# SSB_Transceiver_IF_Amplifier.net
KiCad netlist of a schematic drawn in EAGLE
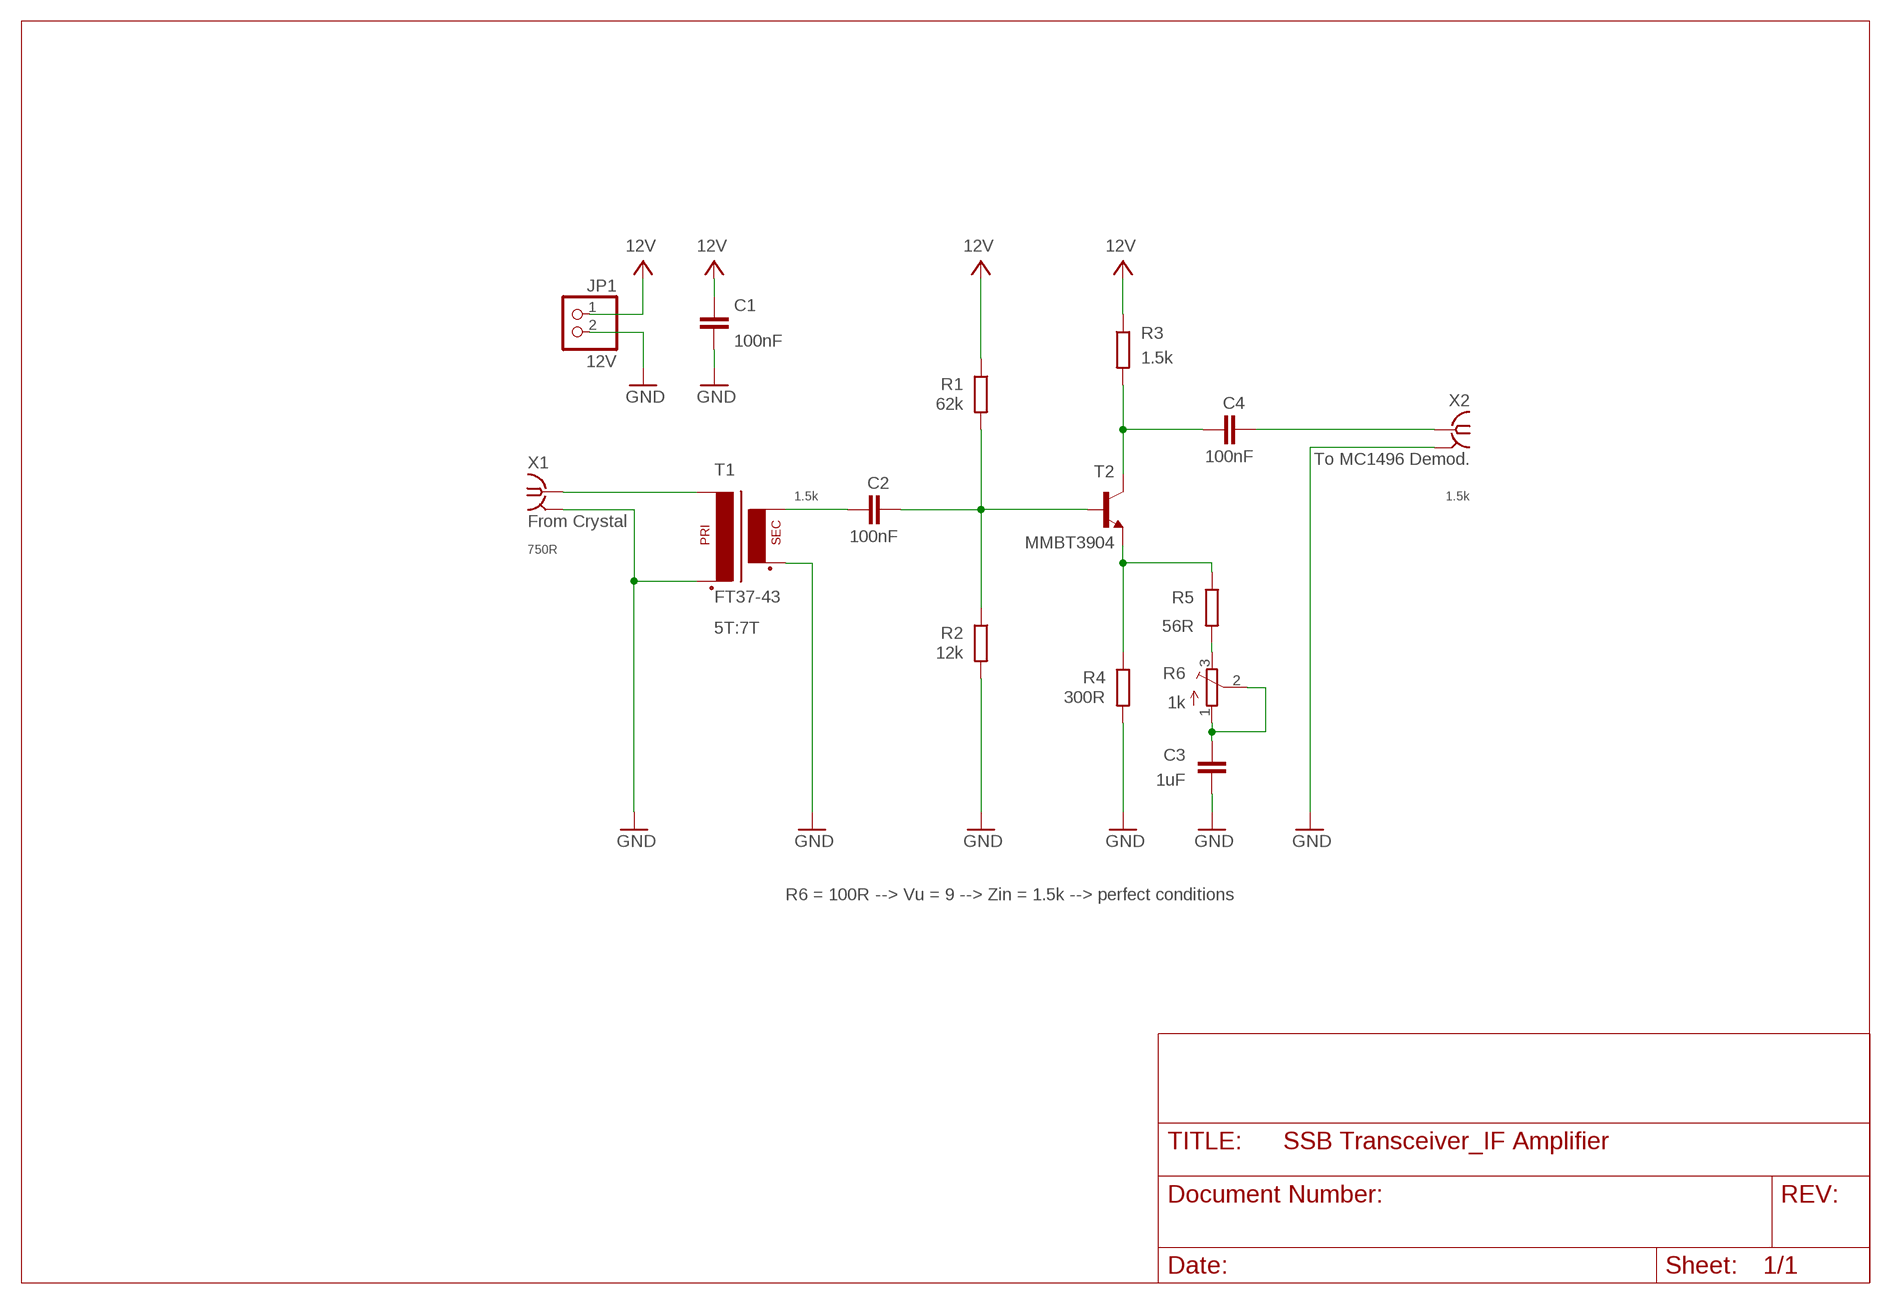
[diagram p0: schematic, sheet 1]

(export (version "E")
  (design (tool "Eeschema 10.0.6"))
  (components
    (comp (ref "C1")
      (value "100nF")
      (footprint "eagle-import:C0805")
      (libsource (lib "eagle-import") (part "C-EUC0805"))
    )
    (comp (ref "C2")
      (value "100nF")
      (footprint "eagle-import:C0805")
      (libsource (lib "eagle-import") (part "C-EUC0805"))
    )
    (comp (ref "C3")
      (value "1uF")
      (footprint "eagle-import:C0805")
      (libsource (lib "eagle-import") (part "C-EUC0805"))
    )
    (comp (ref "C4")
      (value "100nF")
      (footprint "eagle-import:C0805")
      (libsource (lib "eagle-import") (part "C-EUC0805"))
    )
    (comp (ref "JP1")
      (value "12V")
      (footprint "eagle-import:1X02")
      (libsource (lib "eagle-import") (part "PINHD-1X2"))
    )
    (comp (ref "R1")
      (value "62k")
      (footprint "eagle-import:R0805")
      (libsource (lib "eagle-import") (part "R-EU_R0805"))
    )
    (comp (ref "R2")
      (value "12k")
      (footprint "eagle-import:R0805")
      (libsource (lib "eagle-import") (part "R-EU_R0805"))
    )
    (comp (ref "R3")
      (value "1.5k")
      (footprint "eagle-import:R0805")
      (libsource (lib "eagle-import") (part "R-EU_R0805"))
    )
    (comp (ref "R4")
      (value "300R")
      (footprint "eagle-import:R0805")
      (libsource (lib "eagle-import") (part "R-EU_R0805"))
    )
    (comp (ref "R5")
      (value "56R")
      (footprint "eagle-import:R0805")
      (libsource (lib "eagle-import") (part "R-EU_R0805"))
    )
    (comp (ref "R6")
      (value "1k")
      (footprint "eagle-import:3223G")
      (libsource (lib "eagle-import") (part "TRIM_EU-3223G"))
    )
    (comp (ref "T1")
      (value "FT37-43")
      (footprint "eagle-import:FT37-43SMD")
      (libsource (lib "eagle-import") (part "FT37-43"))
    )
    (comp (ref "T2")
      (value "MMBT3904")
      (footprint "eagle-import:SOT23-BEC")
      (libsource (lib "eagle-import") (part "-NPN-SOT23-BECMMBT3904LT1"))
    )
    (comp (ref "X1")
      (value "From Crystal")
      (footprint "eagle-import:J502-ND-142-0711-821_826")
      (fields (field (name "MF") "JOHNSON COMPONENTS") (field (name "MPN") "142-0711-821"))
      (libsource (lib "eagle-import") (part "SMA-PCB-CON142-0711-821/826"))
    )
    (comp (ref "X2")
      (value "To MC1496 Demod.")
      (footprint "eagle-import:J502-ND-142-0711-821_826")
      (fields (field (name "MF") "JOHNSON COMPONENTS") (field (name "MPN") "142-0711-821"))
      (libsource (lib "eagle-import") (part "SMA-PCB-CON142-0711-821/826"))
    )
  )
  (nets
    (net (code "1") (name "12V") (class "Default")
      (node (ref "C1") (pin "2") (pinfunction "2_2") (pintype "passive"))
      (node (ref "JP1") (pin "1") (pinfunction "1_1") (pintype "passive"))
      (node (ref "R1") (pin "1") (pinfunction "1_1") (pintype "passive"))
      (node (ref "R3") (pin "1") (pinfunction "1_1") (pintype "passive"))
    )
    (net (code "2") (name "GND") (class "Default")
      (node (ref "C1") (pin "1") (pinfunction "1_1") (pintype "passive"))
      (node (ref "C3") (pin "1") (pinfunction "1_1") (pintype "passive"))
      (node (ref "JP1") (pin "2") (pinfunction "2_2") (pintype "passive"))
      (node (ref "R2") (pin "2") (pinfunction "2_2") (pintype "passive"))
      (node (ref "R4") (pin "2") (pinfunction "2_2") (pintype "passive"))
      (node (ref "T1") (pin "P$2") (pinfunction "P2_P$2") (pintype "passive"))
      (node (ref "T1") (pin "S$2") (pinfunction "S2_S$2") (pintype "passive"))
      (node (ref "X1") (pin "G@1") (pinfunction "2_G@1") (pintype "passive"))
      (node (ref "X1") (pin "G@2") (pinfunction "2_G@2") (pintype "passive"))
      (node (ref "X1") (pin "G@3") (pinfunction "2_G@3") (pintype "passive"))
      (node (ref "X1") (pin "G@4") (pinfunction "2_G@4") (pintype "passive"))
      (node (ref "X2") (pin "G@1") (pinfunction "2_G@1") (pintype "passive"))
      (node (ref "X2") (pin "G@2") (pinfunction "2_G@2") (pintype "passive"))
      (node (ref "X2") (pin "G@3") (pinfunction "2_G@3") (pintype "passive"))
      (node (ref "X2") (pin "G@4") (pinfunction "2_G@4") (pintype "passive"))
    )
    (net (code "3") (name "Net-(C2-Pad2)") (class "Default")
      (node (ref "C2") (pin "2") (pinfunction "2_2") (pintype "passive"))
      (node (ref "R1") (pin "2") (pinfunction "2_2") (pintype "passive"))
      (node (ref "R2") (pin "1") (pinfunction "1_1") (pintype "passive"))
      (node (ref "T2") (pin "B") (pinfunction "B_B") (pintype "passive"))
    )
    (net (code "4") (name "Net-(C4-Pad1)") (class "Default")
      (node (ref "C4") (pin "1") (pinfunction "1_1") (pintype "passive"))
      (node (ref "R3") (pin "2") (pinfunction "2_2") (pintype "passive"))
      (node (ref "T2") (pin "C") (pinfunction "C_C") (pintype "passive"))
    )
    (net (code "5") (name "Net-(C4-Pad2)") (class "Default")
      (node (ref "C4") (pin "2") (pinfunction "2_2") (pintype "passive"))
      (node (ref "X2") (pin "1") (pinfunction "1_1") (pintype "passive"))
    )
    (net (code "6") (name "Net-(R4-Pad1)") (class "Default")
      (node (ref "R4") (pin "1") (pinfunction "1_1") (pintype "passive"))
      (node (ref "R5") (pin "1") (pinfunction "1_1") (pintype "passive"))
      (node (ref "T2") (pin "E") (pinfunction "E_E") (pintype "passive"))
    )
    (net (code "7") (name "Net-(R6-A)") (class "Default")
      (node (ref "C3") (pin "2") (pinfunction "2_2") (pintype "passive"))
      (node (ref "R6") (pin "1") (pinfunction "A_1") (pintype "passive"))
      (node (ref "R6") (pin "2") (pinfunction "S_2") (pintype "passive"))
    )
    (net (code "8") (name "Net-(R6-E)") (class "Default")
      (node (ref "R5") (pin "2") (pinfunction "2_2") (pintype "passive"))
      (node (ref "R6") (pin "3") (pinfunction "E_3") (pintype "passive"))
    )
    (net (code "9") (name "Net-(T1-P1)") (class "Default")
      (node (ref "T1") (pin "P$1") (pinfunction "P1_P$1") (pintype "passive"))
      (node (ref "X1") (pin "1") (pinfunction "1_1") (pintype "passive"))
    )
    (net (code "10") (name "Net-(T1-S1)") (class "Default")
      (node (ref "C2") (pin "1") (pinfunction "1_1") (pintype "passive"))
      (node (ref "T1") (pin "S$1") (pinfunction "S1_S$1") (pintype "passive"))
    )
  )
)
